# STM8_prog.net
KiCad netlist of a schematic drawn in EAGLE
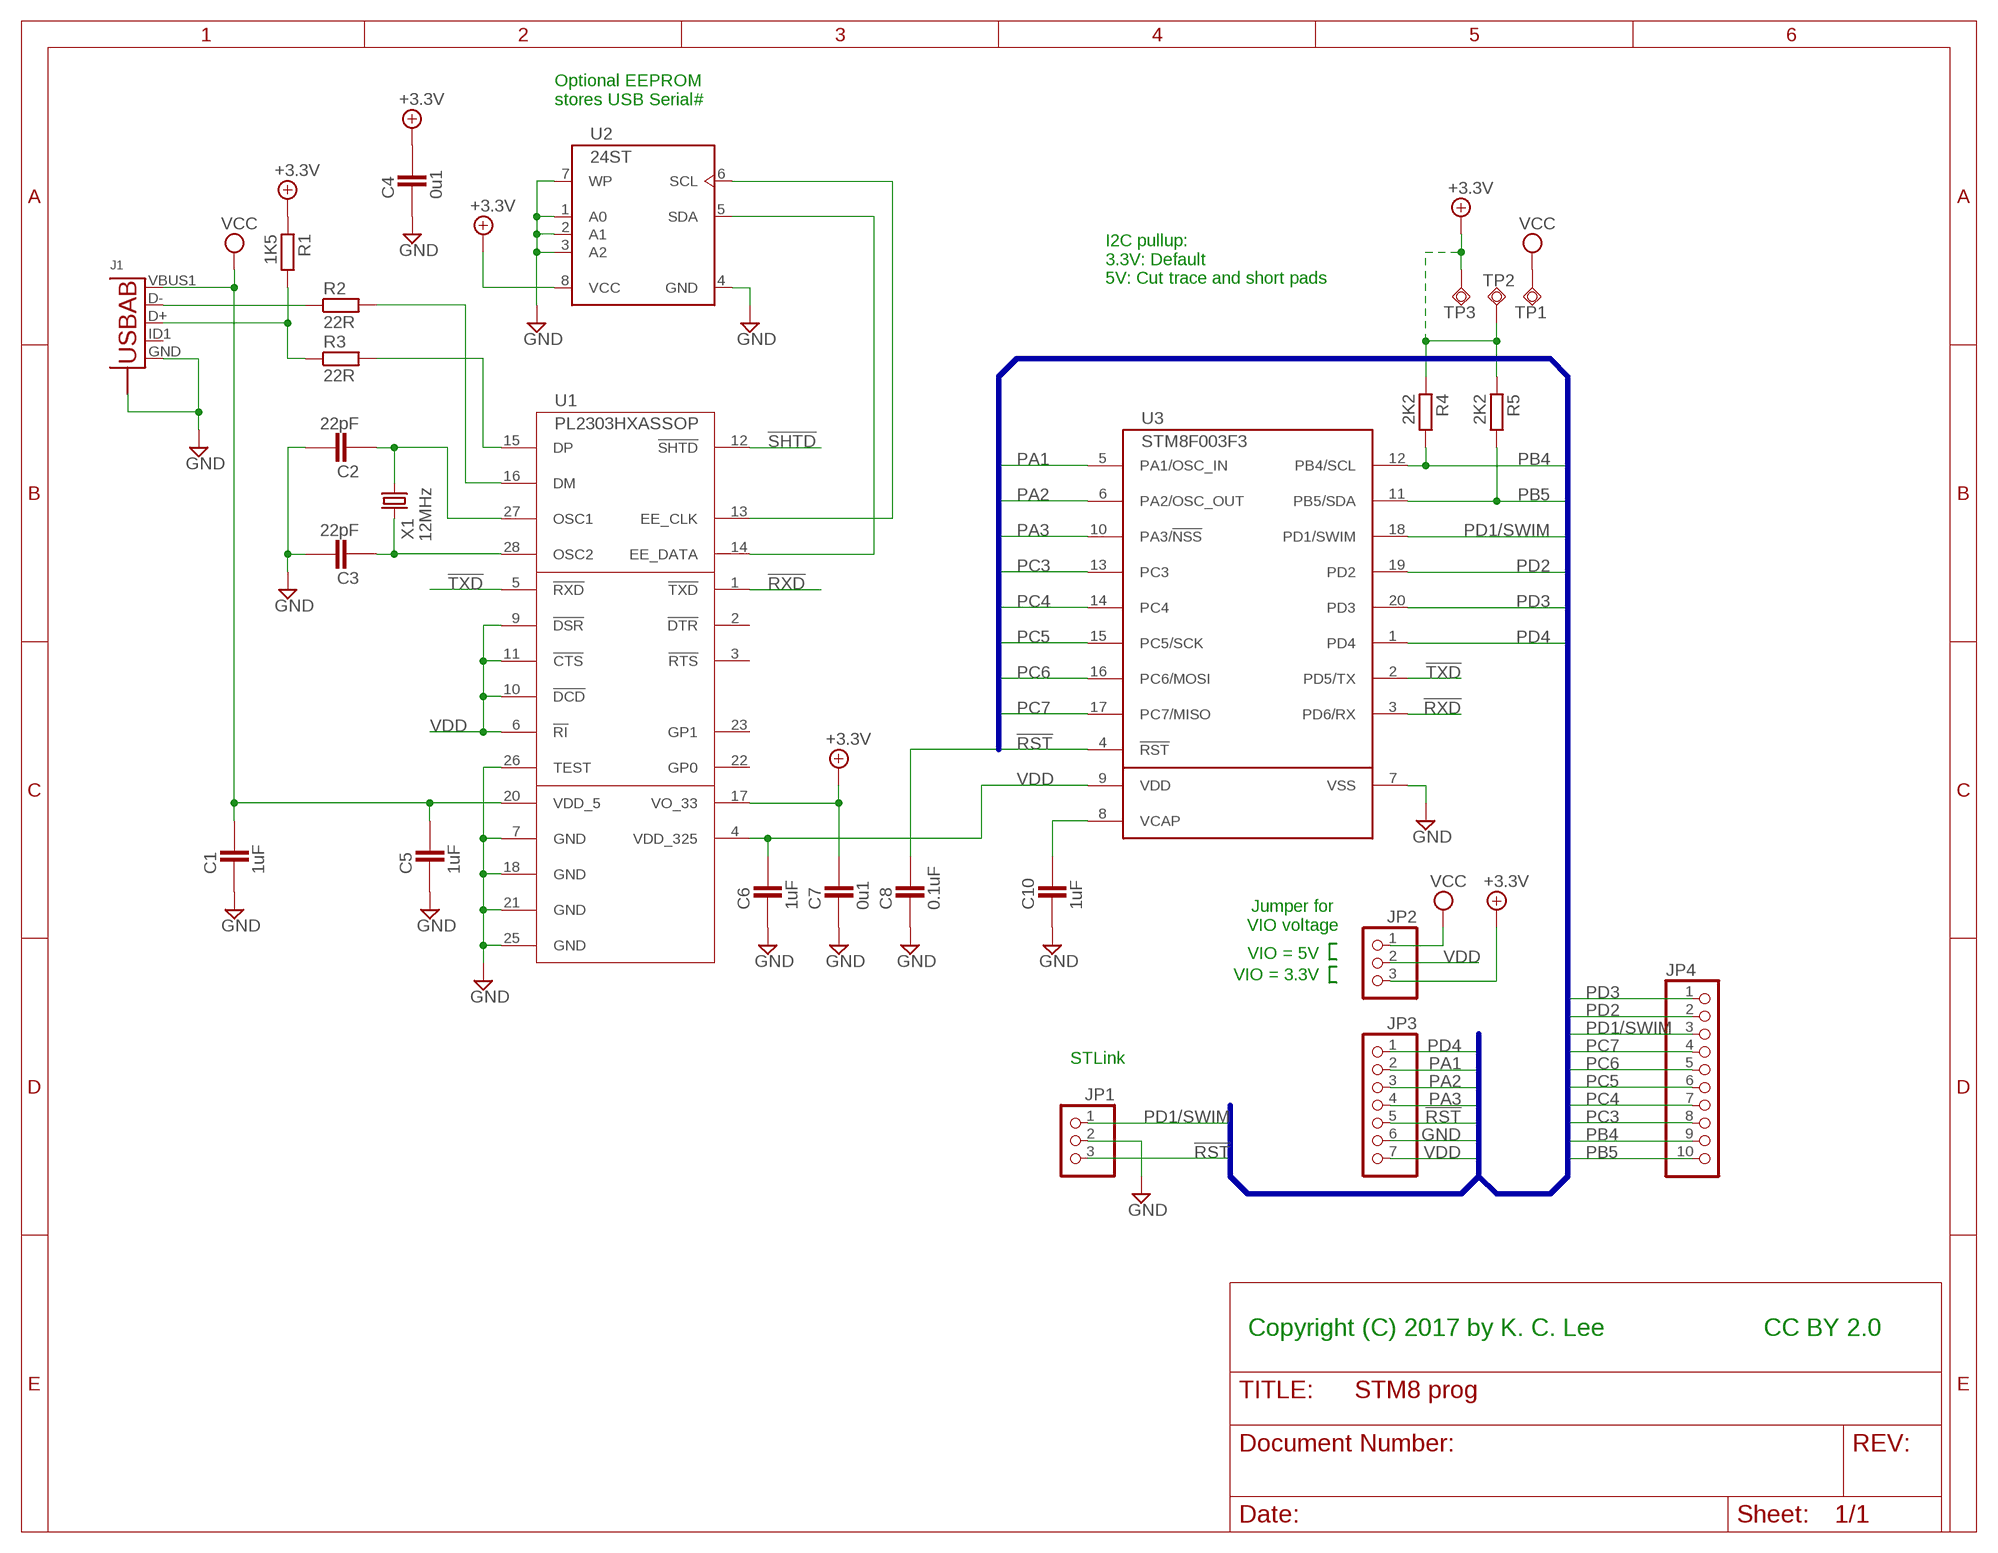
[diagram p0: schematic, sheet 1]

(export (version "E")
  (design (tool "Eeschema 10.0.6"))
  (components
    (comp (ref "C1")
      (value "1uF")
      (footprint "eagle-import:CAPC1608X92N")
      (libsource (lib "eagle-import") (part "CAPACITOR_0603"))
    )
    (comp (ref "C2")
      (value "22pF")
      (footprint "eagle-import:CAPC1608X92N")
      (libsource (lib "eagle-import") (part "CAPACITOR_0603"))
    )
    (comp (ref "C3")
      (value "22pF")
      (footprint "eagle-import:CAPC1608X92N")
      (libsource (lib "eagle-import") (part "CAPACITOR_0603"))
    )
    (comp (ref "C4")
      (value "0u1")
      (footprint "eagle-import:CAPC1608X92N")
      (libsource (lib "eagle-import") (part "CAPACITOR_0603"))
    )
    (comp (ref "C5")
      (value "1uF")
      (footprint "eagle-import:CAPC1608X92N")
      (libsource (lib "eagle-import") (part "CAPACITOR_0603"))
    )
    (comp (ref "C6")
      (value "1uF")
      (footprint "eagle-import:CAPC1608X92N")
      (libsource (lib "eagle-import") (part "CAPACITOR_0603"))
    )
    (comp (ref "C7")
      (value "0u1")
      (footprint "eagle-import:CAPC1608X92N")
      (libsource (lib "eagle-import") (part "CAPACITOR_0603"))
    )
    (comp (ref "C8")
      (value "0.1uF")
      (footprint "eagle-import:CAPC1608X92N")
      (libsource (lib "eagle-import") (part "CAPACITOR_0603"))
    )
    (comp (ref "C10")
      (value "1uF")
      (footprint "eagle-import:CAPC1608X92N")
      (libsource (lib "eagle-import") (part "CAPACITOR_0603"))
    )
    (comp (ref "J1")
      (value "USB-ABBG")
      (footprint "eagle-import:USB-AB-MICRO-SMD_V03_SF")
      (libsource (lib "eagle-import") (part "USB-ABBG"))
    )
    (comp (ref "JP1")
      (value "PINHD-1X3")
      (footprint "eagle-import:1X03")
      (libsource (lib "eagle-import") (part "PINHD-1X3"))
    )
    (comp (ref "JP2")
      (value "PINHD-1X3")
      (footprint "eagle-import:1X03")
      (libsource (lib "eagle-import") (part "PINHD-1X3"))
    )
    (comp (ref "JP3")
      (value "PINHD-1X7_2.54")
      (footprint "eagle-import:1X07")
      (libsource (lib "eagle-import") (part "PINHD-1X7_2.54"))
    )
    (comp (ref "JP4")
      (value "PINHD-1X10")
      (footprint "eagle-import:1X10")
      (libsource (lib "eagle-import") (part "PINHD-1X10"))
    )
    (comp (ref "R1")
      (value "1K5")
      (footprint "eagle-import:RESC1608X55N")
      (libsource (lib "eagle-import") (part "RESISTOR_0603"))
    )
    (comp (ref "R2")
      (value "22R")
      (footprint "eagle-import:RESC1608X55N")
      (libsource (lib "eagle-import") (part "RESISTOR_0603"))
    )
    (comp (ref "R3")
      (value "22R")
      (footprint "eagle-import:RESC1608X55N")
      (libsource (lib "eagle-import") (part "RESISTOR_0603"))
    )
    (comp (ref "R4")
      (value "2K2")
      (footprint "eagle-import:RESC1608X55N")
      (libsource (lib "eagle-import") (part "RESISTOR_0603"))
    )
    (comp (ref "R5")
      (value "2K2")
      (footprint "eagle-import:RESC1608X55N")
      (libsource (lib "eagle-import") (part "RESISTOR_0603"))
    )
    (comp (ref "TP1")
      (value "TPSQTP09SQ")
      (footprint "eagle-import:TP09SQ")
      (libsource (lib "eagle-import") (part "TPSQTP09SQ"))
    )
    (comp (ref "TP2")
      (value "TPSQTP09SQ")
      (footprint "eagle-import:TP09SQ")
      (libsource (lib "eagle-import") (part "TPSQTP09SQ"))
    )
    (comp (ref "TP3")
      (value "TPSQTP09SQ")
      (footprint "eagle-import:TP09SQ")
      (libsource (lib "eagle-import") (part "TPSQTP09SQ"))
    )
    (comp (ref "U1")
      (value "PL2303HXASSOP")
      (footprint "eagle-import:SSOP28DB")
      (libsource (lib "eagle-import") (part "PL2303HXASSOP"))
    )
    (comp (ref "U2")
      (value "24ST")
      (footprint "eagle-import:TSSOP8")
      (libsource (lib "eagle-import") (part "24ST"))
    )
    (comp (ref "U3")
      (value "STM8F003F3")
      (footprint "eagle-import:TSSOP20")
      (libsource (lib "eagle-import") (part "STM8SX03F3"))
    )
    (comp (ref "X1")
      (value "12MHz")
      (footprint "eagle-import:HC49U-V")
      (libsource (lib "eagle-import") (part "CRYSTALHC49U-V"))
    )
  )
  (nets
    (net (code "1") (name "+3.3V") (class "Default")
      (node (ref "C4") (pin "2") (pinfunction "2_2") (pintype "passive"))
      (node (ref "C7") (pin "2") (pinfunction "2_2") (pintype "passive"))
      (node (ref "JP2") (pin "3") (pinfunction "3_3") (pintype "passive"))
      (node (ref "R1") (pin "1") (pinfunction "1_1") (pintype "passive"))
      (node (ref "R4") (pin "1") (pinfunction "1_1") (pintype "passive"))
      (node (ref "R5") (pin "1") (pinfunction "1_1") (pintype "passive"))
      (node (ref "TP2") (pin "TP") (pinfunction "TP_TP") (pintype "input"))
      (node (ref "TP3") (pin "TP") (pinfunction "TP_TP") (pintype "input"))
      (node (ref "U1") (pin "17") (pinfunction "VO_33_17") (pintype "output"))
      (node (ref "U2") (pin "8") (pinfunction "VCC_8") (pintype "power_in"))
    )
    (net (code "2") (name "/PA1") (class "Default")
      (node (ref "JP3") (pin "2") (pinfunction "2_2") (pintype "passive"))
      (node (ref "U3") (pin "5") (pinfunction "PA1/OSC_IN_5") (pintype "input"))
    )
    (net (code "3") (name "/PA2") (class "Default")
      (node (ref "JP3") (pin "3") (pinfunction "3_3") (pintype "passive"))
      (node (ref "U3") (pin "6") (pinfunction "PA2/OSC_OUT_6") (pintype "output"))
    )
    (net (code "4") (name "/PA3") (class "Default")
      (node (ref "JP3") (pin "4") (pinfunction "4_4") (pintype "passive"))
      (node (ref "U3") (pin "10") (pinfunction "PA3/~{NSS}_10") (pintype "bidirectional"))
    )
    (net (code "5") (name "/PB4") (class "Default")
      (node (ref "JP4") (pin "9") (pinfunction "9_9") (pintype "passive"))
      (node (ref "R4") (pin "2") (pinfunction "2_2") (pintype "passive"))
      (node (ref "U3") (pin "12") (pinfunction "PB4/SCL_12") (pintype "bidirectional"))
    )
    (net (code "6") (name "/PB5") (class "Default")
      (node (ref "JP4") (pin "10") (pinfunction "10_10") (pintype "passive"))
      (node (ref "R5") (pin "2") (pinfunction "2_2") (pintype "passive"))
      (node (ref "U3") (pin "11") (pinfunction "PB5/SDA_11") (pintype "bidirectional"))
    )
    (net (code "7") (name "/PC3") (class "Default")
      (node (ref "JP4") (pin "8") (pinfunction "8_8") (pintype "passive"))
      (node (ref "U3") (pin "13") (pinfunction "PC3_13") (pintype "bidirectional"))
    )
    (net (code "8") (name "/PC4") (class "Default")
      (node (ref "JP4") (pin "7") (pinfunction "7_7") (pintype "passive"))
      (node (ref "U3") (pin "14") (pinfunction "PC4_14") (pintype "bidirectional"))
    )
    (net (code "9") (name "/PC5") (class "Default")
      (node (ref "JP4") (pin "6") (pinfunction "6_6") (pintype "passive"))
      (node (ref "U3") (pin "15") (pinfunction "PC5/SCK_15") (pintype "bidirectional"))
    )
    (net (code "10") (name "/PC6") (class "Default")
      (node (ref "JP4") (pin "5") (pinfunction "5_5") (pintype "passive"))
      (node (ref "U3") (pin "16") (pinfunction "PC6/MOSI_16") (pintype "bidirectional"))
    )
    (net (code "11") (name "/PC7") (class "Default")
      (node (ref "JP4") (pin "4") (pinfunction "4_4") (pintype "passive"))
      (node (ref "U3") (pin "17") (pinfunction "PC7/MISO_17") (pintype "bidirectional"))
    )
    (net (code "12") (name "/PD1{slash}SWIM") (class "Default")
      (node (ref "JP1") (pin "1") (pinfunction "1_1") (pintype "passive"))
      (node (ref "JP4") (pin "3") (pinfunction "3_3") (pintype "passive"))
      (node (ref "U3") (pin "18") (pinfunction "PD1/SWIM_18") (pintype "input"))
    )
    (net (code "13") (name "/PD2") (class "Default")
      (node (ref "JP4") (pin "2") (pinfunction "2_2") (pintype "passive"))
      (node (ref "U3") (pin "19") (pinfunction "PD2_19") (pintype "bidirectional"))
    )
    (net (code "14") (name "/PD3") (class "Default")
      (node (ref "JP4") (pin "1") (pinfunction "1_1") (pintype "passive"))
      (node (ref "U3") (pin "20") (pinfunction "PD3_20") (pintype "bidirectional"))
    )
    (net (code "15") (name "/PD4") (class "Default")
      (node (ref "JP3") (pin "1") (pinfunction "1_1") (pintype "passive"))
      (node (ref "U3") (pin "1") (pinfunction "PD4_1") (pintype "bidirectional"))
    )
    (net (code "16") (name "/VDD") (class "Default")
      (node (ref "C6") (pin "2") (pinfunction "2_2") (pintype "passive"))
      (node (ref "JP2") (pin "2") (pinfunction "2_2") (pintype "passive"))
      (node (ref "JP3") (pin "7") (pinfunction "7_7") (pintype "passive"))
      (node (ref "U1") (pin "10") (pinfunction "~{DCD}_10") (pintype "bidirectional"))
      (node (ref "U1") (pin "11") (pinfunction "~{CTS}_11") (pintype "bidirectional"))
      (node (ref "U1") (pin "4") (pinfunction "VDD_325_4") (pintype "input"))
      (node (ref "U1") (pin "6") (pinfunction "~{RI}_6") (pintype "bidirectional"))
      (node (ref "U1") (pin "9") (pinfunction "~{DSR}_9") (pintype "bidirectional"))
      (node (ref "U3") (pin "9") (pinfunction "VDD_9") (pintype "input"))
    )
    (net (code "17") (name "/~{RST}") (class "Default")
      (node (ref "C8") (pin "2") (pinfunction "2_2") (pintype "passive"))
      (node (ref "JP1") (pin "3") (pinfunction "3_3") (pintype "passive"))
      (node (ref "JP3") (pin "5") (pinfunction "5_5") (pintype "passive"))
      (node (ref "U3") (pin "4") (pinfunction "~{RST}_4") (pintype "input"))
    )
    (net (code "18") (name "/~{RXD}") (class "Default")
      (node (ref "U1") (pin "1") (pinfunction "~{TXD}_1") (pintype "output"))
      (node (ref "U3") (pin "3") (pinfunction "PD6/RX_3") (pintype "bidirectional"))
    )
    (net (code "19") (name "/~{SHTD}") (class "Default")
      (node (ref "U1") (pin "12") (pinfunction "~{SHTD}_12") (pintype "output"))
    )
    (net (code "20") (name "/~{TXD}") (class "Default")
      (node (ref "U1") (pin "5") (pinfunction "~{RXD}_5") (pintype "input"))
      (node (ref "U3") (pin "2") (pinfunction "PD5/TX_2") (pintype "bidirectional"))
    )
    (net (code "21") (name "GND") (class "Default")
      (node (ref "C1") (pin "1") (pinfunction "1_1") (pintype "passive"))
      (node (ref "C10") (pin "1") (pinfunction "1_1") (pintype "passive"))
      (node (ref "C2") (pin "2") (pinfunction "2_2") (pintype "passive"))
      (node (ref "C3") (pin "2") (pinfunction "2_2") (pintype "passive"))
      (node (ref "C4") (pin "1") (pinfunction "1_1") (pintype "passive"))
      (node (ref "C5") (pin "1") (pinfunction "1_1") (pintype "passive"))
      (node (ref "C6") (pin "1") (pinfunction "1_1") (pintype "passive"))
      (node (ref "C7") (pin "1") (pinfunction "1_1") (pintype "passive"))
      (node (ref "C8") (pin "1") (pinfunction "1_1") (pintype "passive"))
      (node (ref "J1") (pin "GND") (pinfunction "GND_GND") (pintype "bidirectional"))
      (node (ref "J1") (pin "S1") (pinfunction "S_S1") (pintype "bidirectional"))
      (node (ref "J1") (pin "S2") (pinfunction "S_S2") (pintype "bidirectional"))
      (node (ref "J1") (pin "S3") (pinfunction "S_S3") (pintype "bidirectional"))
      (node (ref "J1") (pin "S4") (pinfunction "S_S4") (pintype "bidirectional"))
      (node (ref "JP1") (pin "2") (pinfunction "2_2") (pintype "passive"))
      (node (ref "JP3") (pin "6") (pinfunction "6_6") (pintype "passive"))
      (node (ref "U1") (pin "18") (pinfunction "GND_18") (pintype "bidirectional"))
      (node (ref "U1") (pin "21") (pinfunction "GND_21") (pintype "bidirectional"))
      (node (ref "U1") (pin "25") (pinfunction "GND_25") (pintype "bidirectional"))
      (node (ref "U1") (pin "26") (pinfunction "TEST_26") (pintype "input"))
      (node (ref "U1") (pin "7") (pinfunction "GND_7") (pintype "input"))
      (node (ref "U2") (pin "1") (pinfunction "A0_1") (pintype "bidirectional"))
      (node (ref "U2") (pin "2") (pinfunction "A1_2") (pintype "bidirectional"))
      (node (ref "U2") (pin "3") (pinfunction "A2_3") (pintype "bidirectional"))
      (node (ref "U2") (pin "4") (pinfunction "GND_4") (pintype "power_in"))
      (node (ref "U2") (pin "7") (pinfunction "WP_7") (pintype "bidirectional"))
      (node (ref "U3") (pin "7") (pinfunction "VSS_7") (pintype "input"))
    )
    (net (code "22") (name "Net-(J1-PadD+)") (class "Default")
      (node (ref "J1") (pin "D+") (pinfunction "D+_D+") (pintype "bidirectional"))
      (node (ref "R1") (pin "2") (pinfunction "2_2") (pintype "passive"))
      (node (ref "R3") (pin "1") (pinfunction "1_1") (pintype "passive"))
    )
    (net (code "23") (name "Net-(J1-PadD-)") (class "Default")
      (node (ref "J1") (pin "D-") (pinfunction "D-_D-") (pintype "bidirectional"))
      (node (ref "R2") (pin "1") (pinfunction "1_1") (pintype "passive"))
    )
    (net (code "24") (name "Net-(U1-DM)") (class "Default")
      (node (ref "R2") (pin "2") (pinfunction "2_2") (pintype "passive"))
      (node (ref "U1") (pin "16") (pinfunction "DM_16") (pintype "bidirectional"))
    )
    (net (code "25") (name "Net-(U1-DP)") (class "Default")
      (node (ref "R3") (pin "2") (pinfunction "2_2") (pintype "passive"))
      (node (ref "U1") (pin "15") (pinfunction "DP_15") (pintype "bidirectional"))
    )
    (net (code "26") (name "Net-(U1-EE_CLK)") (class "Default")
      (node (ref "U1") (pin "13") (pinfunction "EE_CLK_13") (pintype "bidirectional"))
      (node (ref "U2") (pin "6") (pinfunction "SCL_6") (pintype "input"))
    )
    (net (code "27") (name "Net-(U1-EE_DATA)") (class "Default")
      (node (ref "U1") (pin "14") (pinfunction "EE_DATA_14") (pintype "bidirectional"))
      (node (ref "U2") (pin "5") (pinfunction "SDA_5") (pintype "bidirectional"))
    )
    (net (code "28") (name "Net-(U1-OSC1)") (class "Default")
      (node (ref "C2") (pin "1") (pinfunction "1_1") (pintype "passive"))
      (node (ref "U1") (pin "27") (pinfunction "OSC1_27") (pintype "input"))
      (node (ref "X1") (pin "1") (pinfunction "1_1") (pintype "passive"))
    )
    (net (code "29") (name "Net-(U1-OSC2)") (class "Default")
      (node (ref "C3") (pin "1") (pinfunction "1_1") (pintype "passive"))
      (node (ref "U1") (pin "28") (pinfunction "OSC2_28") (pintype "bidirectional"))
      (node (ref "X1") (pin "2") (pinfunction "2_2") (pintype "passive"))
    )
    (net (code "30") (name "Net-(U3-VCAP)") (class "Default")
      (node (ref "C10") (pin "2") (pinfunction "2_2") (pintype "passive"))
      (node (ref "U3") (pin "8") (pinfunction "VCAP_8") (pintype "input"))
    )
    (net (code "31") (name "VCC") (class "Default")
      (node (ref "C1") (pin "2") (pinfunction "2_2") (pintype "passive"))
      (node (ref "C5") (pin "2") (pinfunction "2_2") (pintype "passive"))
      (node (ref "J1") (pin "VBUS1") (pinfunction "VBUS_VBUS1") (pintype "bidirectional"))
      (node (ref "JP2") (pin "1") (pinfunction "1_1") (pintype "passive"))
      (node (ref "TP1") (pin "TP") (pinfunction "TP_TP") (pintype "input"))
      (node (ref "U1") (pin "20") (pinfunction "VDD_5_20") (pintype "input"))
    )
    (net (code "32") (name "unconnected-(J1-USBID-PadID1)") (class "Default")
      (node (ref "J1") (pin "ID1") (pinfunction "USBID_ID1") (pintype "bidirectional"))
    )
    (net (code "33") (name "unconnected-(U1-GP0-Pad22)") (class "Default")
      (node (ref "U1") (pin "22") (pinfunction "GP0_22") (pintype "bidirectional"))
    )
    (net (code "34") (name "unconnected-(U1-GP1-Pad23)") (class "Default")
      (node (ref "U1") (pin "23") (pinfunction "GP1_23") (pintype "bidirectional"))
    )
    (net (code "35") (name "unconnected-(U1-~{DTR}-Pad2)") (class "Default")
      (node (ref "U1") (pin "2") (pinfunction "~{DTR}_2") (pintype "output"))
    )
    (net (code "36") (name "unconnected-(U1-~{RTS}-Pad3)") (class "Default")
      (node (ref "U1") (pin "3") (pinfunction "~{RTS}_3") (pintype "output"))
    )
  )
)
